# FTM_SCH.net
KiCad netlist of a schematic drawn in Altium Designer
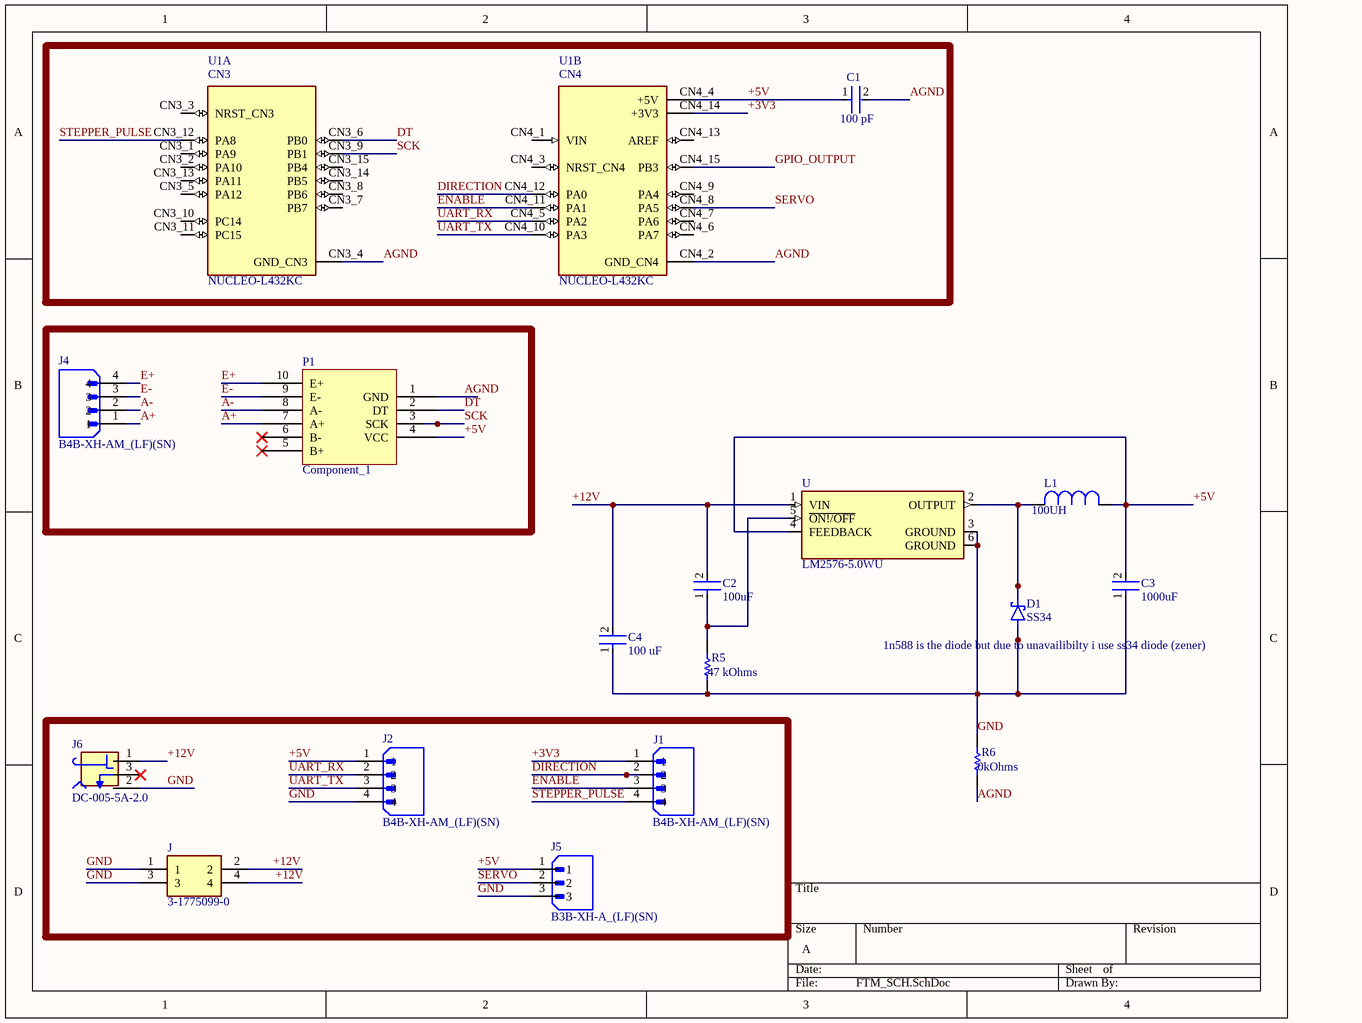
[diagram p0: FTM_SCH.SchDoc]

(export (version "E")
  (design (tool "Eeschema 10.0.6"))
  (components
    (comp (ref "C1")
      (value "C1206C101J1GACTU")
      (footprint "FP-C1206C-EB-MFG")
      (description "CAP CER 100PF 100V C0G/NP0 1206")
      (fields
        (field (name "MANUFACTURER") "KEMET")
        (field (name "CAPACITANCE") "100 pF")
        (field (name "TOLERANCE") "0.05")
      )
      (libsource (lib "Altium Content Vault") (part "b4654b650e69147ec39a6b967a45e02"))
    )
    (comp (ref "C2")
      (value "C1206C101J1GACTU")
      (footprint "FP-C1206C-EB-MFG")
      (description "CAP CER 100PF 100V C0G/NP0 1206")
      (fields
        (field (name "MANUFACTURER") "KEMET")
        (field (name "CAPACITANCE") "100uF")
        (field (name "TOLERANCE") "0.05")
      )
      (libsource (lib "Altium Content Vault") (part "b4654b650e69147ec39a6b967a45e02"))
    )
    (comp (ref "C3")
      (value "C1206C101J1GACTU")
      (footprint "FP-C1206C-EB-MFG")
      (description "CAP CER 100PF 100V C0G/NP0 1206")
      (fields
        (field (name "MANUFACTURER") "KEMET")
        (field (name "CAPACITANCE") "1000uF")
        (field (name "TOLERANCE") "0.05")
      )
      (libsource (lib "Altium Content Vault") (part "b4654b650e69147ec39a6b967a45e02"))
    )
    (comp (ref "C4")
      (value "C1206C101J1GACTU")
      (footprint "FP-C1206C-EB-MFG")
      (description "CAP CER 100PF 100V C0G/NP0 1206")
      (fields
        (field (name "MANUFACTURER") "KEMET")
        (field (name "CAPACITANCE") "100 uF")
        (field (name "TOLERANCE") "0.05")
      )
      (libsource (lib "Altium Content Vault") (part "b4654b650e69147ec39a6b967a45e02"))
    )
    (comp (ref "D1")
      (value "SS34")
      (footprint "DIOM7959X265N")
      (description "Diode Schottky 40 V 3A Surface Mount SMC (DO-214AB)")
      (fields (field (name "MF") "onsemi"))
      (libsource (lib "SS34") (part "SS34"))
    )
    (comp (ref "J")
      (value "3-1775099-0")
      (footprint "TE_3-1775099-0")
      (description "Conn Power PL 4 POS 4.2mm Solder ST Thru-Hole 4 Terminal 1 Port Tray")
      (fields (field (name "MF") "TE Connectivity"))
      (libsource (lib "3-1775099-0") (part "3-1775099-0"))
    )
    (comp (ref "J1")
      (value "B4B-XH-AM_(LF)(SN)")
      (footprint "JST_B4B-XH-AM_(LF)(SN)")
      (description "Conn Shrouded Header HDR 4 POS 2.5mm Solder ST Top Entry Thru-Hole Box")
      (fields (field (name "MF") "JST Corporation") (field (name "MP") "B4B-XH-AM (LF)(SN)"))
      (libsource (lib "B4B-XH-AM__LF__SN_") (part "B4B-XH-AM_(LF)(SN)"))
    )
    (comp (ref "J2")
      (value "B4B-XH-AM_(LF)(SN)")
      (footprint "JST_B4B-XH-AM_(LF)(SN)")
      (description "Conn Shrouded Header HDR 4 POS 2.5mm Solder ST Top Entry Thru-Hole Box")
      (fields (field (name "MF") "JST Corporation") (field (name "MP") "B4B-XH-AM (LF)(SN)"))
      (libsource (lib "B4B-XH-AM__LF__SN_") (part "B4B-XH-AM_(LF)(SN)"))
    )
    (comp (ref "J4")
      (value "B4B-XH-AM_(LF)(SN)")
      (footprint "JST_B4B-XH-AM_(LF)(SN)")
      (description "Conn Shrouded Header HDR 4 POS 2.5mm Solder ST Top Entry Thru-Hole Box")
      (fields (field (name "MF") "JST Corporation") (field (name "MP") "B4B-XH-AM (LF)(SN)"))
      (libsource (lib "") (part "B4B-XH-AM_(LF)(SN)_1"))
    )
    (comp (ref "J5")
      (value "B3B-XH-A_(LF)(SN)")
      (footprint "JST_B3B-XH-A (LF)(SN)")
      (description "Connector Header Through Hole 3 position 0.098 (2.50mm)")
      (fields (field (name "MF") "JST Sales America Inc.") (field (name "MP") "B3B-XH-A (LF)(SN)"))
      (libsource (lib "B3B-XH-A__LF__SN_") (part "B3B-XH-A_(LF)(SN)"))
    )
    (comp (ref "J6")
      (value "DC-005-5A-2.0")
      (footprint "XKB_DC-005-5A-2.0")
      (description "DC Power Receptacle Jack, Through Holeï¼ŒRight Angle")
      (fields (field (name "MF") "XKB Industrial Precision"))
      (libsource (lib "DC-005-5A-2.0") (part "DC-005-5A-2.0"))
    )
    (comp (ref "L1")
      (value "100UH")
      (footprint "IND_CDRH127/LDNP-470MC_SUM")
      (description "47 ÂµH Shielded - Inductor 3.25 A 78mOhm Max Nonstandard")
      (fields (field (name "MF") "Sumida America") (field (name "MP") "CDRH127/LDNP-470MC"))
      (libsource (lib "CDRH127_LDNP-470MC") (part "CDRH127/LDNP-470MC"))
    )
    (comp (ref "P1")
      (value "Component_1")
      (footprint "PCBComponent_1")
      (libsource (lib "Schlib1") (part "Component_1"))
    )
    (comp (ref "R5")
      (value "47 kOhms")
      (footprint "RESC3216X70X50LL05T20")
      (fields (field (name "MANUFACTURER") "Panasonic") (field (name "PART NUMBER") "ERJ-8ENF1001V"))
      (libsource (lib "Altium Content Vault") (part "RES"))
    )
    (comp (ref "R6")
      (value "0kOhms")
      (footprint "RESC3216X70X50LL05T20")
      (fields (field (name "MANUFACTURER") "Panasonic") (field (name "PART NUMBER") "ERJ-8ENF1001V"))
      (libsource (lib "Altium Content Vault") (part "RES"))
    )
    (comp (ref "U")
      (value "LM2576-5.0WU")
      (footprint "DPAK6P170_1524X459L254X81N")
      (fields (field (name "MF") "Microchip"))
      (libsource (lib "LM2576-5.0WU") (part "LM2576-5.0WU"))
    )
    (comp (ref "U1")
      (value "NUCLEO-L432KC")
      (footprint "MODULE_NUCLEO-L432KC")
      (description "STM32 Nucleo-32 development board with STM32L432KC MCU, supports Arduino connectivity")
      (libsource (lib "NUCLEO-L432KC") (part "NUCLEO-L432KC"))
    )
  )
  (nets
    (net (code "1") (name "/+3V3") (class "Default")
      (node (ref "J1") (pin "1") (pinfunction "1_1") (pintype "passive"))
      (node (ref "U1") (pin "CN4_14") (pinfunction "+3V3_CN4_14") (pintype "power_in"))
    )
    (net (code "2") (name "/+5V") (class "Default")
      (node (ref "C1") (pin "1") (pinfunction "1_1") (pintype "passive"))
      (node (ref "C3") (pin "2") (pinfunction "2_2") (pintype "passive"))
      (node (ref "J2") (pin "1") (pinfunction "1_1") (pintype "passive"))
      (node (ref "J5") (pin "1") (pinfunction "1_1") (pintype "passive"))
      (node (ref "L1") (pin "1") (pinfunction "1_1") (pintype "passive"))
      (node (ref "P1") (pin "4") (pinfunction "VCC_4") (pintype "passive"))
      (node (ref "U") (pin "4") (pinfunction "FEEDBACK_4") (pintype "bidirectional"))
      (node (ref "U1") (pin "CN4_4") (pinfunction "+5V_CN4_4") (pintype "power_in"))
    )
    (net (code "3") (name "/+12V") (class "Default")
      (node (ref "C2") (pin "2") (pinfunction "2_2") (pintype "passive"))
      (node (ref "C4") (pin "2") (pinfunction "2_2") (pintype "passive"))
      (node (ref "J") (pin "2") (pinfunction "2_2") (pintype "passive"))
      (node (ref "J") (pin "4") (pinfunction "4_4") (pintype "passive"))
      (node (ref "J6") (pin "1") (pinfunction "1_1") (pintype "passive"))
      (node (ref "U") (pin "1") (pinfunction "VIN_1") (pintype "input"))
    )
    (net (code "4") (name "/A+") (class "Default")
      (node (ref "J4") (pin "1") (pinfunction "1_1") (pintype "passive"))
      (node (ref "P1") (pin "7") (pinfunction "A+_7") (pintype "passive"))
    )
    (net (code "5") (name "/A-") (class "Default")
      (node (ref "J4") (pin "2") (pinfunction "2_2") (pintype "passive"))
      (node (ref "P1") (pin "8") (pinfunction "A-_8") (pintype "passive"))
    )
    (net (code "6") (name "/AGND") (class "Default")
      (node (ref "C1") (pin "2") (pinfunction "2_2") (pintype "passive"))
      (node (ref "P1") (pin "1") (pinfunction "GND_1") (pintype "passive"))
      (node (ref "R6") (pin "1") (pinfunction "1_1") (pintype "passive"))
      (node (ref "U1") (pin "CN3_4") (pinfunction "GND_CN3_CN3_4") (pintype "power_in"))
      (node (ref "U1") (pin "CN4_2") (pinfunction "GND_CN4_CN4_2") (pintype "power_in"))
    )
    (net (code "7") (name "/DIRECTION") (class "Default")
      (node (ref "J1") (pin "2") (pinfunction "2_2") (pintype "passive"))
      (node (ref "U1") (pin "CN4_12") (pinfunction "PA0_CN4_12") (pintype "bidirectional"))
    )
    (net (code "8") (name "/DT") (class "Default")
      (node (ref "P1") (pin "2") (pinfunction "DT_2") (pintype "passive"))
      (node (ref "U1") (pin "CN3_6") (pinfunction "PB0_CN3_6") (pintype "bidirectional"))
    )
    (net (code "9") (name "/E+") (class "Default")
      (node (ref "J4") (pin "4") (pinfunction "4_4") (pintype "passive"))
      (node (ref "P1") (pin "10") (pinfunction "E+_10") (pintype "passive"))
    )
    (net (code "10") (name "/E-") (class "Default")
      (node (ref "J4") (pin "3") (pinfunction "3_3") (pintype "passive"))
      (node (ref "P1") (pin "9") (pinfunction "E-_9") (pintype "passive"))
    )
    (net (code "11") (name "/ENABLE") (class "Default")
      (node (ref "J1") (pin "3") (pinfunction "3_3") (pintype "passive"))
      (node (ref "U1") (pin "CN4_11") (pinfunction "PA1_CN4_11") (pintype "bidirectional"))
    )
    (net (code "12") (name "/GND") (class "Default")
      (node (ref "C3") (pin "1") (pinfunction "1_1") (pintype "passive"))
      (node (ref "C4") (pin "1") (pinfunction "1_1") (pintype "passive"))
      (node (ref "D1") (pin "A") (pinfunction "A_A") (pintype "passive"))
      (node (ref "J") (pin "1") (pinfunction "1_1") (pintype "passive"))
      (node (ref "J") (pin "3") (pinfunction "3_3") (pintype "passive"))
      (node (ref "J2") (pin "4") (pinfunction "4_4") (pintype "passive"))
      (node (ref "J5") (pin "3") (pinfunction "3_3") (pintype "passive"))
      (node (ref "J6") (pin "2") (pinfunction "2_2") (pintype "passive"))
      (node (ref "R5") (pin "1") (pinfunction "1_1") (pintype "passive"))
      (node (ref "R6") (pin "2") (pinfunction "2_2") (pintype "passive"))
      (node (ref "U") (pin "3") (pinfunction "GROUND_3") (pintype "power_in"))
      (node (ref "U") (pin "6") (pinfunction "GROUND_6") (pintype "power_in"))
    )
    (net (code "13") (name "/GPIO_OUTPUT") (class "Default")
      (node (ref "U1") (pin "CN4_15") (pinfunction "PB3_CN4_15") (pintype "bidirectional"))
    )
    (net (code "14") (name "/SCK") (class "Default")
      (node (ref "P1") (pin "3") (pinfunction "SCK_3") (pintype "passive"))
      (node (ref "U1") (pin "CN3_9") (pinfunction "PB1_CN3_9") (pintype "bidirectional"))
    )
    (net (code "15") (name "/SERVO") (class "Default")
      (node (ref "J5") (pin "2") (pinfunction "2_2") (pintype "passive"))
      (node (ref "U1") (pin "CN4_8") (pinfunction "PA5_CN4_8") (pintype "bidirectional"))
    )
    (net (code "16") (name "/STEPPER_PULSE") (class "Default")
      (node (ref "J1") (pin "4") (pinfunction "4_4") (pintype "passive"))
      (node (ref "U1") (pin "CN3_12") (pinfunction "PA8_CN3_12") (pintype "bidirectional"))
    )
    (net (code "17") (name "/UART_RX") (class "Default")
      (node (ref "J2") (pin "2") (pinfunction "2_2") (pintype "passive"))
      (node (ref "U1") (pin "CN4_5") (pinfunction "PA2_CN4_5") (pintype "bidirectional"))
    )
    (net (code "18") (name "/UART_TX") (class "Default")
      (node (ref "J2") (pin "3") (pinfunction "3_3") (pintype "passive"))
      (node (ref "U1") (pin "CN4_10") (pinfunction "PA3_CN4_10") (pintype "bidirectional"))
    )
    (net (code "19") (name "Net-(D1-K)") (class "Default")
      (node (ref "D1") (pin "C") (pinfunction "K_C") (pintype "passive"))
      (node (ref "L1") (pin "2") (pinfunction "2_2") (pintype "passive"))
      (node (ref "U") (pin "2") (pinfunction "OUTPUT_2") (pintype "output"))
    )
    (net (code "20") (name "Net-(U-~{ON!{slash}OFF})") (class "Default")
      (node (ref "C2") (pin "1") (pinfunction "1_1") (pintype "passive"))
      (node (ref "R5") (pin "2") (pinfunction "2_2") (pintype "passive"))
      (node (ref "U") (pin "5") (pinfunction "~{ON!/OFF}_5") (pintype "input"))
    )
    (net (code "21") (name "unconnected-(J6-Pad3)") (class "Default")
      (node (ref "J6") (pin "3") (pinfunction "3_3") (pintype "passive+no_connect"))
    )
    (net (code "22") (name "unconnected-(P1-B+-Pad5)") (class "Default")
      (node (ref "P1") (pin "5") (pinfunction "B+_5") (pintype "passive+no_connect"))
    )
    (net (code "23") (name "unconnected-(P1-B--Pad6)") (class "Default")
      (node (ref "P1") (pin "6") (pinfunction "B-_6") (pintype "passive+no_connect"))
    )
    (net (code "24") (name "unconnected-(U1A-NRST_CN3-PadCN3_3)") (class "Default")
      (node (ref "U1") (pin "CN3_3") (pinfunction "NRST_CN3_CN3_3") (pintype "bidirectional"))
    )
    (net (code "25") (name "unconnected-(U1A-PA9-PadCN3_1)") (class "Default")
      (node (ref "U1") (pin "CN3_1") (pinfunction "PA9_CN3_1") (pintype "bidirectional"))
    )
    (net (code "26") (name "unconnected-(U1A-PA10-PadCN3_2)") (class "Default")
      (node (ref "U1") (pin "CN3_2") (pinfunction "PA10_CN3_2") (pintype "bidirectional"))
    )
    (net (code "27") (name "unconnected-(U1A-PA11-PadCN3_13)") (class "Default")
      (node (ref "U1") (pin "CN3_13") (pinfunction "PA11_CN3_13") (pintype "bidirectional"))
    )
    (net (code "28") (name "unconnected-(U1A-PA12-PadCN3_5)") (class "Default")
      (node (ref "U1") (pin "CN3_5") (pinfunction "PA12_CN3_5") (pintype "bidirectional"))
    )
    (net (code "29") (name "unconnected-(U1A-PB4-PadCN3_15)") (class "Default")
      (node (ref "U1") (pin "CN3_15") (pinfunction "PB4_CN3_15") (pintype "bidirectional"))
    )
    (net (code "30") (name "unconnected-(U1A-PB5-PadCN3_14)") (class "Default")
      (node (ref "U1") (pin "CN3_14") (pinfunction "PB5_CN3_14") (pintype "bidirectional"))
    )
    (net (code "31") (name "unconnected-(U1A-PB6-PadCN3_8)") (class "Default")
      (node (ref "U1") (pin "CN3_8") (pinfunction "PB6_CN3_8") (pintype "bidirectional"))
    )
    (net (code "32") (name "unconnected-(U1A-PB7-PadCN3_7)") (class "Default")
      (node (ref "U1") (pin "CN3_7") (pinfunction "PB7_CN3_7") (pintype "bidirectional"))
    )
    (net (code "33") (name "unconnected-(U1A-PC14-PadCN3_10)") (class "Default")
      (node (ref "U1") (pin "CN3_10") (pinfunction "PC14_CN3_10") (pintype "bidirectional"))
    )
    (net (code "34") (name "unconnected-(U1A-PC15-PadCN3_11)") (class "Default")
      (node (ref "U1") (pin "CN3_11") (pinfunction "PC15_CN3_11") (pintype "bidirectional"))
    )
    (net (code "35") (name "unconnected-(U1B-AREF-PadCN4_13)") (class "Default")
      (node (ref "U1") (pin "CN4_13") (pinfunction "AREF_CN4_13") (pintype "bidirectional"))
    )
    (net (code "36") (name "unconnected-(U1B-NRST_CN4-PadCN4_3)") (class "Default")
      (node (ref "U1") (pin "CN4_3") (pinfunction "NRST_CN4_CN4_3") (pintype "bidirectional"))
    )
    (net (code "37") (name "unconnected-(U1B-PA4-PadCN4_9)") (class "Default")
      (node (ref "U1") (pin "CN4_9") (pinfunction "PA4_CN4_9") (pintype "bidirectional"))
    )
    (net (code "38") (name "unconnected-(U1B-PA6-PadCN4_7)") (class "Default")
      (node (ref "U1") (pin "CN4_7") (pinfunction "PA6_CN4_7") (pintype "bidirectional"))
    )
    (net (code "39") (name "unconnected-(U1B-PA7-PadCN4_6)") (class "Default")
      (node (ref "U1") (pin "CN4_6") (pinfunction "PA7_CN4_6") (pintype "bidirectional"))
    )
    (net (code "40") (name "unconnected-(U1B-VIN-PadCN4_1)") (class "Default")
      (node (ref "U1") (pin "CN4_1") (pinfunction "VIN_CN4_1") (pintype "input"))
    )
  )
)
